# piezo-layer_v0_1-R002.net
KiCad netlist of a schematic drawn in EAGLE
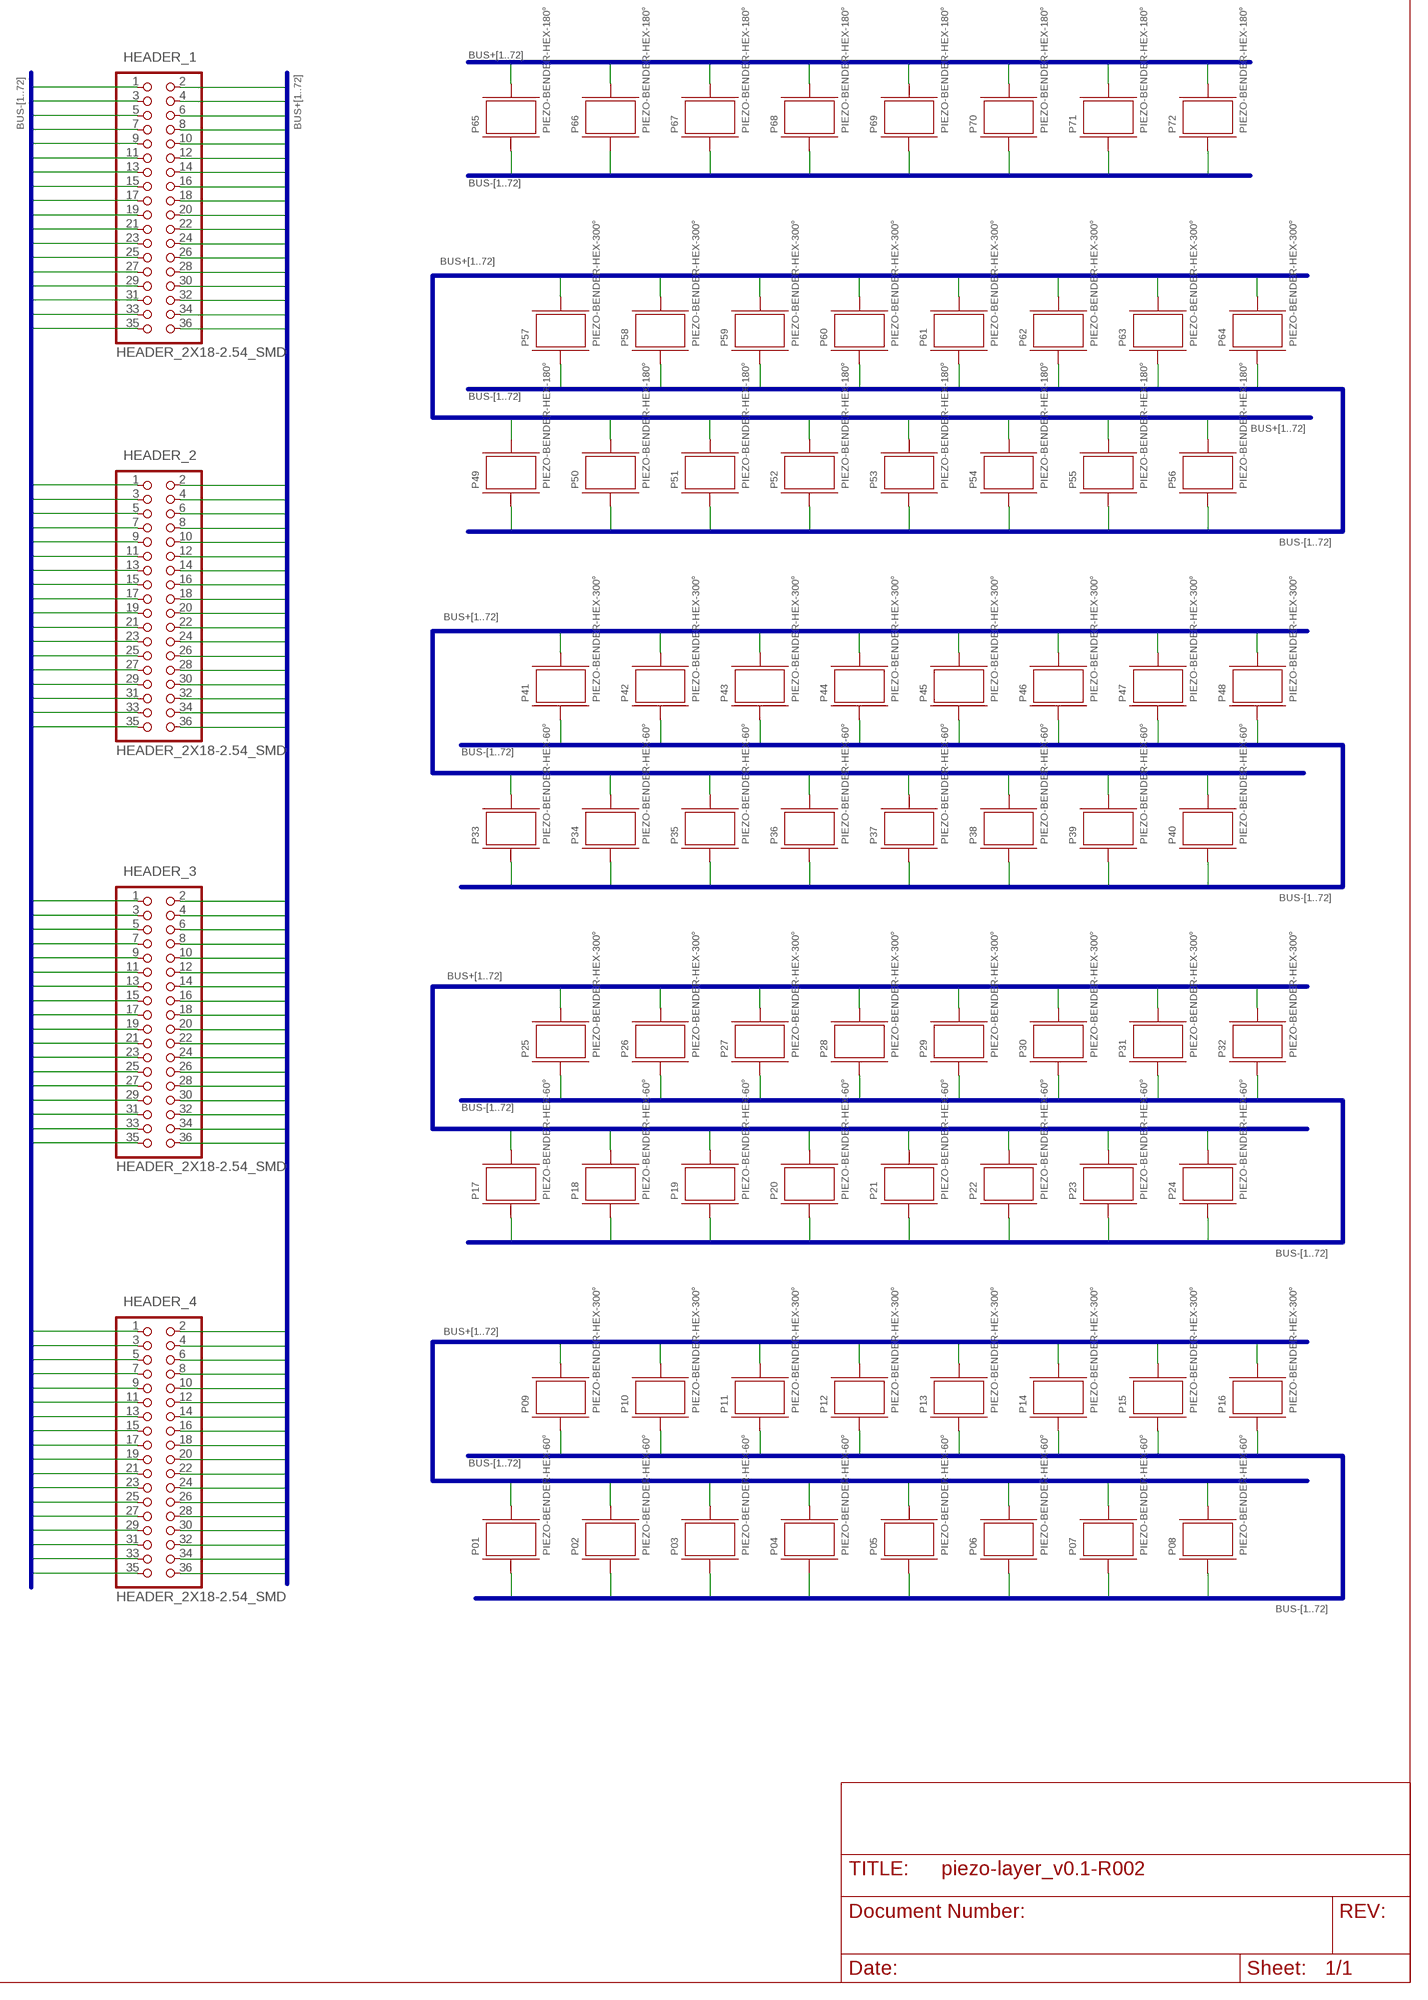
[diagram p0: schematic, sheet 1]

(export (version "E")
  (design (tool "Eeschema 10.0.6"))
  (components
    (comp (ref "HEADER_1")
      (value "HEADER_2X18-2.54_SMD")
      (footprint "eagle-import:2X18_2.54_SMD")
      (libsource (lib "eagle-import") (part "HEADER_2X18-2.54_SMD"))
    )
    (comp (ref "HEADER_2")
      (value "HEADER_2X18-2.54_SMD")
      (footprint "eagle-import:2X18_2.54_SMD")
      (libsource (lib "eagle-import") (part "HEADER_2X18-2.54_SMD"))
    )
    (comp (ref "HEADER_3")
      (value "HEADER_2X18-2.54_SMD")
      (footprint "eagle-import:2X18_2.54_SMD")
      (libsource (lib "eagle-import") (part "HEADER_2X18-2.54_SMD"))
    )
    (comp (ref "HEADER_4")
      (value "HEADER_2X18-2.54_SMD")
      (footprint "eagle-import:2X18_2.54_SMD")
      (libsource (lib "eagle-import") (part "HEADER_2X18-2.54_SMD"))
    )
    (comp (ref "P01")
      (value "PIEZO-BENDER-HEX-60°")
      (footprint "eagle-import:PIEZO-BENDER-HEX_16MM_60°")
      (libsource (lib "eagle-import") (part "PIEZO-BENDER-HEX-60°"))
    )
    (comp (ref "P02")
      (value "PIEZO-BENDER-HEX-60°")
      (footprint "eagle-import:PIEZO-BENDER-HEX_16MM_60°")
      (libsource (lib "eagle-import") (part "PIEZO-BENDER-HEX-60°"))
    )
    (comp (ref "P03")
      (value "PIEZO-BENDER-HEX-60°")
      (footprint "eagle-import:PIEZO-BENDER-HEX_16MM_60°")
      (libsource (lib "eagle-import") (part "PIEZO-BENDER-HEX-60°"))
    )
    (comp (ref "P04")
      (value "PIEZO-BENDER-HEX-60°")
      (footprint "eagle-import:PIEZO-BENDER-HEX_16MM_60°")
      (libsource (lib "eagle-import") (part "PIEZO-BENDER-HEX-60°"))
    )
    (comp (ref "P05")
      (value "PIEZO-BENDER-HEX-60°")
      (footprint "eagle-import:PIEZO-BENDER-HEX_16MM_60°")
      (libsource (lib "eagle-import") (part "PIEZO-BENDER-HEX-60°"))
    )
    (comp (ref "P06")
      (value "PIEZO-BENDER-HEX-60°")
      (footprint "eagle-import:PIEZO-BENDER-HEX_16MM_60°")
      (libsource (lib "eagle-import") (part "PIEZO-BENDER-HEX-60°"))
    )
    (comp (ref "P07")
      (value "PIEZO-BENDER-HEX-60°")
      (footprint "eagle-import:PIEZO-BENDER-HEX_16MM_60°")
      (libsource (lib "eagle-import") (part "PIEZO-BENDER-HEX-60°"))
    )
    (comp (ref "P08")
      (value "PIEZO-BENDER-HEX-60°")
      (footprint "eagle-import:PIEZO-BENDER-HEX_16MM_60°")
      (libsource (lib "eagle-import") (part "PIEZO-BENDER-HEX-60°"))
    )
    (comp (ref "P09")
      (value "PIEZO-BENDER-HEX-300°")
      (footprint "eagle-import:PIEZO-BENDER-HEX_16MM_300°")
      (libsource (lib "eagle-import") (part "PIEZO-BENDER-HEX-300°"))
    )
    (comp (ref "P10")
      (value "PIEZO-BENDER-HEX-300°")
      (footprint "eagle-import:PIEZO-BENDER-HEX_16MM_300°")
      (libsource (lib "eagle-import") (part "PIEZO-BENDER-HEX-300°"))
    )
    (comp (ref "P11")
      (value "PIEZO-BENDER-HEX-300°")
      (footprint "eagle-import:PIEZO-BENDER-HEX_16MM_300°")
      (libsource (lib "eagle-import") (part "PIEZO-BENDER-HEX-300°"))
    )
    (comp (ref "P12")
      (value "PIEZO-BENDER-HEX-300°")
      (footprint "eagle-import:PIEZO-BENDER-HEX_16MM_300°")
      (libsource (lib "eagle-import") (part "PIEZO-BENDER-HEX-300°"))
    )
    (comp (ref "P13")
      (value "PIEZO-BENDER-HEX-300°")
      (footprint "eagle-import:PIEZO-BENDER-HEX_16MM_300°")
      (libsource (lib "eagle-import") (part "PIEZO-BENDER-HEX-300°"))
    )
    (comp (ref "P14")
      (value "PIEZO-BENDER-HEX-300°")
      (footprint "eagle-import:PIEZO-BENDER-HEX_16MM_300°")
      (libsource (lib "eagle-import") (part "PIEZO-BENDER-HEX-300°"))
    )
    (comp (ref "P15")
      (value "PIEZO-BENDER-HEX-300°")
      (footprint "eagle-import:PIEZO-BENDER-HEX_16MM_300°")
      (libsource (lib "eagle-import") (part "PIEZO-BENDER-HEX-300°"))
    )
    (comp (ref "P16")
      (value "PIEZO-BENDER-HEX-300°")
      (footprint "eagle-import:PIEZO-BENDER-HEX_16MM_300°")
      (libsource (lib "eagle-import") (part "PIEZO-BENDER-HEX-300°"))
    )
    (comp (ref "P17")
      (value "PIEZO-BENDER-HEX-60°")
      (footprint "eagle-import:PIEZO-BENDER-HEX_16MM_60°")
      (libsource (lib "eagle-import") (part "PIEZO-BENDER-HEX-60°"))
    )
    (comp (ref "P18")
      (value "PIEZO-BENDER-HEX-60°")
      (footprint "eagle-import:PIEZO-BENDER-HEX_16MM_60°")
      (libsource (lib "eagle-import") (part "PIEZO-BENDER-HEX-60°"))
    )
    (comp (ref "P19")
      (value "PIEZO-BENDER-HEX-60°")
      (footprint "eagle-import:PIEZO-BENDER-HEX_16MM_60°")
      (libsource (lib "eagle-import") (part "PIEZO-BENDER-HEX-60°"))
    )
    (comp (ref "P20")
      (value "PIEZO-BENDER-HEX-60°")
      (footprint "eagle-import:PIEZO-BENDER-HEX_16MM_60°")
      (libsource (lib "eagle-import") (part "PIEZO-BENDER-HEX-60°"))
    )
    (comp (ref "P21")
      (value "PIEZO-BENDER-HEX-60°")
      (footprint "eagle-import:PIEZO-BENDER-HEX_16MM_60°")
      (libsource (lib "eagle-import") (part "PIEZO-BENDER-HEX-60°"))
    )
    (comp (ref "P22")
      (value "PIEZO-BENDER-HEX-60°")
      (footprint "eagle-import:PIEZO-BENDER-HEX_16MM_60°")
      (libsource (lib "eagle-import") (part "PIEZO-BENDER-HEX-60°"))
    )
    (comp (ref "P23")
      (value "PIEZO-BENDER-HEX-60°")
      (footprint "eagle-import:PIEZO-BENDER-HEX_16MM_60°")
      (libsource (lib "eagle-import") (part "PIEZO-BENDER-HEX-60°"))
    )
    (comp (ref "P24")
      (value "PIEZO-BENDER-HEX-60°")
      (footprint "eagle-import:PIEZO-BENDER-HEX_16MM_60°")
      (libsource (lib "eagle-import") (part "PIEZO-BENDER-HEX-60°"))
    )
    (comp (ref "P25")
      (value "PIEZO-BENDER-HEX-300°")
      (footprint "eagle-import:PIEZO-BENDER-HEX_16MM_300°")
      (libsource (lib "eagle-import") (part "PIEZO-BENDER-HEX-300°"))
    )
    (comp (ref "P26")
      (value "PIEZO-BENDER-HEX-300°")
      (footprint "eagle-import:PIEZO-BENDER-HEX_16MM_300°")
      (libsource (lib "eagle-import") (part "PIEZO-BENDER-HEX-300°"))
    )
    (comp (ref "P27")
      (value "PIEZO-BENDER-HEX-300°")
      (footprint "eagle-import:PIEZO-BENDER-HEX_16MM_300°")
      (libsource (lib "eagle-import") (part "PIEZO-BENDER-HEX-300°"))
    )
    (comp (ref "P28")
      (value "PIEZO-BENDER-HEX-300°")
      (footprint "eagle-import:PIEZO-BENDER-HEX_16MM_300°")
      (libsource (lib "eagle-import") (part "PIEZO-BENDER-HEX-300°"))
    )
    (comp (ref "P29")
      (value "PIEZO-BENDER-HEX-300°")
      (footprint "eagle-import:PIEZO-BENDER-HEX_16MM_300°")
      (libsource (lib "eagle-import") (part "PIEZO-BENDER-HEX-300°"))
    )
    (comp (ref "P30")
      (value "PIEZO-BENDER-HEX-300°")
      (footprint "eagle-import:PIEZO-BENDER-HEX_16MM_300°")
      (libsource (lib "eagle-import") (part "PIEZO-BENDER-HEX-300°"))
    )
    (comp (ref "P31")
      (value "PIEZO-BENDER-HEX-300°")
      (footprint "eagle-import:PIEZO-BENDER-HEX_16MM_300°")
      (libsource (lib "eagle-import") (part "PIEZO-BENDER-HEX-300°"))
    )
    (comp (ref "P32")
      (value "PIEZO-BENDER-HEX-300°")
      (footprint "eagle-import:PIEZO-BENDER-HEX_16MM_300°")
      (libsource (lib "eagle-import") (part "PIEZO-BENDER-HEX-300°"))
    )
    (comp (ref "P33")
      (value "PIEZO-BENDER-HEX-60°")
      (footprint "eagle-import:PIEZO-BENDER-HEX_16MM_60°")
      (libsource (lib "eagle-import") (part "PIEZO-BENDER-HEX-60°"))
    )
    (comp (ref "P34")
      (value "PIEZO-BENDER-HEX-60°")
      (footprint "eagle-import:PIEZO-BENDER-HEX_16MM_60°")
      (libsource (lib "eagle-import") (part "PIEZO-BENDER-HEX-60°"))
    )
    (comp (ref "P35")
      (value "PIEZO-BENDER-HEX-60°")
      (footprint "eagle-import:PIEZO-BENDER-HEX_16MM_60°")
      (libsource (lib "eagle-import") (part "PIEZO-BENDER-HEX-60°"))
    )
    (comp (ref "P36")
      (value "PIEZO-BENDER-HEX-60°")
      (footprint "eagle-import:PIEZO-BENDER-HEX_16MM_60°")
      (libsource (lib "eagle-import") (part "PIEZO-BENDER-HEX-60°"))
    )
    (comp (ref "P37")
      (value "PIEZO-BENDER-HEX-60°")
      (footprint "eagle-import:PIEZO-BENDER-HEX_16MM_60°")
      (libsource (lib "eagle-import") (part "PIEZO-BENDER-HEX-60°"))
    )
    (comp (ref "P38")
      (value "PIEZO-BENDER-HEX-60°")
      (footprint "eagle-import:PIEZO-BENDER-HEX_16MM_60°")
      (libsource (lib "eagle-import") (part "PIEZO-BENDER-HEX-60°"))
    )
    (comp (ref "P39")
      (value "PIEZO-BENDER-HEX-60°")
      (footprint "eagle-import:PIEZO-BENDER-HEX_16MM_60°")
      (libsource (lib "eagle-import") (part "PIEZO-BENDER-HEX-60°"))
    )
    (comp (ref "P40")
      (value "PIEZO-BENDER-HEX-60°")
      (footprint "eagle-import:PIEZO-BENDER-HEX_16MM_60°")
      (libsource (lib "eagle-import") (part "PIEZO-BENDER-HEX-60°"))
    )
    (comp (ref "P41")
      (value "PIEZO-BENDER-HEX-300°")
      (footprint "eagle-import:PIEZO-BENDER-HEX_16MM_300°")
      (libsource (lib "eagle-import") (part "PIEZO-BENDER-HEX-300°"))
    )
    (comp (ref "P42")
      (value "PIEZO-BENDER-HEX-300°")
      (footprint "eagle-import:PIEZO-BENDER-HEX_16MM_300°")
      (libsource (lib "eagle-import") (part "PIEZO-BENDER-HEX-300°"))
    )
    (comp (ref "P43")
      (value "PIEZO-BENDER-HEX-300°")
      (footprint "eagle-import:PIEZO-BENDER-HEX_16MM_300°")
      (libsource (lib "eagle-import") (part "PIEZO-BENDER-HEX-300°"))
    )
    (comp (ref "P44")
      (value "PIEZO-BENDER-HEX-300°")
      (footprint "eagle-import:PIEZO-BENDER-HEX_16MM_300°")
      (libsource (lib "eagle-import") (part "PIEZO-BENDER-HEX-300°"))
    )
    (comp (ref "P45")
      (value "PIEZO-BENDER-HEX-300°")
      (footprint "eagle-import:PIEZO-BENDER-HEX_16MM_300°")
      (libsource (lib "eagle-import") (part "PIEZO-BENDER-HEX-300°"))
    )
    (comp (ref "P46")
      (value "PIEZO-BENDER-HEX-300°")
      (footprint "eagle-import:PIEZO-BENDER-HEX_16MM_300°")
      (libsource (lib "eagle-import") (part "PIEZO-BENDER-HEX-300°"))
    )
    (comp (ref "P47")
      (value "PIEZO-BENDER-HEX-300°")
      (footprint "eagle-import:PIEZO-BENDER-HEX_16MM_300°")
      (libsource (lib "eagle-import") (part "PIEZO-BENDER-HEX-300°"))
    )
    (comp (ref "P48")
      (value "PIEZO-BENDER-HEX-300°")
      (footprint "eagle-import:PIEZO-BENDER-HEX_16MM_300°")
      (libsource (lib "eagle-import") (part "PIEZO-BENDER-HEX-300°"))
    )
    (comp (ref "P49")
      (value "PIEZO-BENDER-HEX-180°")
      (footprint "eagle-import:PIEZO-BENDER-HEX_16MM_180°")
      (libsource (lib "eagle-import") (part "PIEZO-BENDER-HEX-180°"))
    )
    (comp (ref "P50")
      (value "PIEZO-BENDER-HEX-180°")
      (footprint "eagle-import:PIEZO-BENDER-HEX_16MM_180°")
      (libsource (lib "eagle-import") (part "PIEZO-BENDER-HEX-180°"))
    )
    (comp (ref "P51")
      (value "PIEZO-BENDER-HEX-180°")
      (footprint "eagle-import:PIEZO-BENDER-HEX_16MM_180°")
      (libsource (lib "eagle-import") (part "PIEZO-BENDER-HEX-180°"))
    )
    (comp (ref "P52")
      (value "PIEZO-BENDER-HEX-180°")
      (footprint "eagle-import:PIEZO-BENDER-HEX_16MM_180°")
      (libsource (lib "eagle-import") (part "PIEZO-BENDER-HEX-180°"))
    )
    (comp (ref "P53")
      (value "PIEZO-BENDER-HEX-180°")
      (footprint "eagle-import:PIEZO-BENDER-HEX_16MM_180°")
      (libsource (lib "eagle-import") (part "PIEZO-BENDER-HEX-180°"))
    )
    (comp (ref "P54")
      (value "PIEZO-BENDER-HEX-180°")
      (footprint "eagle-import:PIEZO-BENDER-HEX_16MM_180°")
      (libsource (lib "eagle-import") (part "PIEZO-BENDER-HEX-180°"))
    )
    (comp (ref "P55")
      (value "PIEZO-BENDER-HEX-180°")
      (footprint "eagle-import:PIEZO-BENDER-HEX_16MM_180°")
      (libsource (lib "eagle-import") (part "PIEZO-BENDER-HEX-180°"))
    )
    (comp (ref "P56")
      (value "PIEZO-BENDER-HEX-180°")
      (footprint "eagle-import:PIEZO-BENDER-HEX_16MM_180°")
      (libsource (lib "eagle-import") (part "PIEZO-BENDER-HEX-180°"))
    )
    (comp (ref "P57")
      (value "PIEZO-BENDER-HEX-300°")
      (footprint "eagle-import:PIEZO-BENDER-HEX_16MM_300°")
      (libsource (lib "eagle-import") (part "PIEZO-BENDER-HEX-300°"))
    )
    (comp (ref "P58")
      (value "PIEZO-BENDER-HEX-300°")
      (footprint "eagle-import:PIEZO-BENDER-HEX_16MM_300°")
      (libsource (lib "eagle-import") (part "PIEZO-BENDER-HEX-300°"))
    )
    (comp (ref "P59")
      (value "PIEZO-BENDER-HEX-300°")
      (footprint "eagle-import:PIEZO-BENDER-HEX_16MM_300°")
      (libsource (lib "eagle-import") (part "PIEZO-BENDER-HEX-300°"))
    )
    (comp (ref "P60")
      (value "PIEZO-BENDER-HEX-300°")
      (footprint "eagle-import:PIEZO-BENDER-HEX_16MM_300°")
      (libsource (lib "eagle-import") (part "PIEZO-BENDER-HEX-300°"))
    )
    (comp (ref "P61")
      (value "PIEZO-BENDER-HEX-300°")
      (footprint "eagle-import:PIEZO-BENDER-HEX_16MM_300°")
      (libsource (lib "eagle-import") (part "PIEZO-BENDER-HEX-300°"))
    )
    (comp (ref "P62")
      (value "PIEZO-BENDER-HEX-300°")
      (footprint "eagle-import:PIEZO-BENDER-HEX_16MM_300°")
      (libsource (lib "eagle-import") (part "PIEZO-BENDER-HEX-300°"))
    )
    (comp (ref "P63")
      (value "PIEZO-BENDER-HEX-300°")
      (footprint "eagle-import:PIEZO-BENDER-HEX_16MM_300°")
      (libsource (lib "eagle-import") (part "PIEZO-BENDER-HEX-300°"))
    )
    (comp (ref "P64")
      (value "PIEZO-BENDER-HEX-300°")
      (footprint "eagle-import:PIEZO-BENDER-HEX_16MM_300°")
      (libsource (lib "eagle-import") (part "PIEZO-BENDER-HEX-300°"))
    )
    (comp (ref "P65")
      (value "PIEZO-BENDER-HEX-180°")
      (footprint "eagle-import:PIEZO-BENDER-HEX_16MM_180°")
      (libsource (lib "eagle-import") (part "PIEZO-BENDER-HEX-180°"))
    )
    (comp (ref "P66")
      (value "PIEZO-BENDER-HEX-180°")
      (footprint "eagle-import:PIEZO-BENDER-HEX_16MM_180°")
      (libsource (lib "eagle-import") (part "PIEZO-BENDER-HEX-180°"))
    )
    (comp (ref "P67")
      (value "PIEZO-BENDER-HEX-180°")
      (footprint "eagle-import:PIEZO-BENDER-HEX_16MM_180°")
      (libsource (lib "eagle-import") (part "PIEZO-BENDER-HEX-180°"))
    )
    (comp (ref "P68")
      (value "PIEZO-BENDER-HEX-180°")
      (footprint "eagle-import:PIEZO-BENDER-HEX_16MM_180°")
      (libsource (lib "eagle-import") (part "PIEZO-BENDER-HEX-180°"))
    )
    (comp (ref "P69")
      (value "PIEZO-BENDER-HEX-180°")
      (footprint "eagle-import:PIEZO-BENDER-HEX_16MM_180°")
      (libsource (lib "eagle-import") (part "PIEZO-BENDER-HEX-180°"))
    )
    (comp (ref "P70")
      (value "PIEZO-BENDER-HEX-180°")
      (footprint "eagle-import:PIEZO-BENDER-HEX_16MM_180°")
      (libsource (lib "eagle-import") (part "PIEZO-BENDER-HEX-180°"))
    )
    (comp (ref "P71")
      (value "PIEZO-BENDER-HEX-180°")
      (footprint "eagle-import:PIEZO-BENDER-HEX_16MM_180°")
      (libsource (lib "eagle-import") (part "PIEZO-BENDER-HEX-180°"))
    )
    (comp (ref "P72")
      (value "PIEZO-BENDER-HEX-180°")
      (footprint "eagle-import:PIEZO-BENDER-HEX_16MM_180°")
      (libsource (lib "eagle-import") (part "PIEZO-BENDER-HEX-180°"))
    )
  )
  (nets
    (net (code "1") (name "/BUS+1") (class "Default")
      (node (ref "HEADER_1") (pin "18") (pinfunction "18_18") (pintype "passive"))
      (node (ref "P01") (pin "TIP1") (pinfunction "+_1_TIP1") (pintype "bidirectional"))
    )
    (net (code "2") (name "/BUS+2") (class "Default")
      (node (ref "HEADER_1") (pin "36") (pinfunction "36_36") (pintype "passive"))
      (node (ref "P02") (pin "TIP1") (pinfunction "+_1_TIP1") (pintype "bidirectional"))
    )
    (net (code "3") (name "/BUS+3") (class "Default")
      (node (ref "HEADER_2") (pin "18") (pinfunction "18_18") (pintype "passive"))
      (node (ref "P03") (pin "TIP1") (pinfunction "+_1_TIP1") (pintype "bidirectional"))
    )
    (net (code "4") (name "/BUS+4") (class "Default")
      (node (ref "HEADER_2") (pin "36") (pinfunction "36_36") (pintype "passive"))
      (node (ref "P04") (pin "TIP1") (pinfunction "+_1_TIP1") (pintype "bidirectional"))
    )
    (net (code "5") (name "/BUS+5") (class "Default")
      (node (ref "HEADER_3") (pin "18") (pinfunction "18_18") (pintype "passive"))
      (node (ref "P05") (pin "TIP1") (pinfunction "+_1_TIP1") (pintype "bidirectional"))
    )
    (net (code "6") (name "/BUS+6") (class "Default")
      (node (ref "HEADER_3") (pin "36") (pinfunction "36_36") (pintype "passive"))
      (node (ref "P06") (pin "TIP1") (pinfunction "+_1_TIP1") (pintype "bidirectional"))
    )
    (net (code "7") (name "/BUS+7") (class "Default")
      (node (ref "HEADER_4") (pin "18") (pinfunction "18_18") (pintype "passive"))
      (node (ref "P07") (pin "TIP1") (pinfunction "+_1_TIP1") (pintype "bidirectional"))
    )
    (net (code "8") (name "/BUS+8") (class "Default")
      (node (ref "HEADER_4") (pin "36") (pinfunction "36_36") (pintype "passive"))
      (node (ref "P08") (pin "TIP1") (pinfunction "+_1_TIP1") (pintype "bidirectional"))
    )
    (net (code "9") (name "/BUS+9") (class "Default")
      (node (ref "HEADER_1") (pin "16") (pinfunction "16_16") (pintype "passive"))
      (node (ref "P09") (pin "TIP1") (pinfunction "+_1_TIP1") (pintype "bidirectional"))
    )
    (net (code "10") (name "/BUS+10") (class "Default")
      (node (ref "HEADER_1") (pin "34") (pinfunction "34_34") (pintype "passive"))
      (node (ref "P10") (pin "TIP1") (pinfunction "+_1_TIP1") (pintype "bidirectional"))
    )
    (net (code "11") (name "/BUS+11") (class "Default")
      (node (ref "HEADER_2") (pin "16") (pinfunction "16_16") (pintype "passive"))
      (node (ref "P11") (pin "TIP1") (pinfunction "+_1_TIP1") (pintype "bidirectional"))
    )
    (net (code "12") (name "/BUS+12") (class "Default")
      (node (ref "HEADER_2") (pin "34") (pinfunction "34_34") (pintype "passive"))
      (node (ref "P12") (pin "TIP1") (pinfunction "+_1_TIP1") (pintype "bidirectional"))
    )
    (net (code "13") (name "/BUS+13") (class "Default")
      (node (ref "HEADER_3") (pin "16") (pinfunction "16_16") (pintype "passive"))
      (node (ref "P13") (pin "TIP1") (pinfunction "+_1_TIP1") (pintype "bidirectional"))
    )
    (net (code "14") (name "/BUS+14") (class "Default")
      (node (ref "HEADER_3") (pin "34") (pinfunction "34_34") (pintype "passive"))
      (node (ref "P14") (pin "TIP1") (pinfunction "+_1_TIP1") (pintype "bidirectional"))
    )
    (net (code "15") (name "/BUS+15") (class "Default")
      (node (ref "HEADER_4") (pin "16") (pinfunction "16_16") (pintype "passive"))
      (node (ref "P15") (pin "TIP1") (pinfunction "+_1_TIP1") (pintype "bidirectional"))
    )
    (net (code "16") (name "/BUS+16") (class "Default")
      (node (ref "HEADER_4") (pin "34") (pinfunction "34_34") (pintype "passive"))
      (node (ref "P16") (pin "TIP1") (pinfunction "+_1_TIP1") (pintype "bidirectional"))
    )
    (net (code "17") (name "/BUS+17") (class "Default")
      (node (ref "HEADER_1") (pin "14") (pinfunction "14_14") (pintype "passive"))
      (node (ref "P17") (pin "TIP1") (pinfunction "+_1_TIP1") (pintype "bidirectional"))
    )
    (net (code "18") (name "/BUS+18") (class "Default")
      (node (ref "HEADER_1") (pin "32") (pinfunction "32_32") (pintype "passive"))
      (node (ref "P18") (pin "TIP1") (pinfunction "+_1_TIP1") (pintype "bidirectional"))
    )
    (net (code "19") (name "/BUS+19") (class "Default")
      (node (ref "HEADER_2") (pin "14") (pinfunction "14_14") (pintype "passive"))
      (node (ref "P19") (pin "TIP1") (pinfunction "+_1_TIP1") (pintype "bidirectional"))
    )
    (net (code "20") (name "/BUS+20") (class "Default")
      (node (ref "HEADER_2") (pin "32") (pinfunction "32_32") (pintype "passive"))
      (node (ref "P20") (pin "TIP1") (pinfunction "+_1_TIP1") (pintype "bidirectional"))
    )
    (net (code "21") (name "/BUS+21") (class "Default")
      (node (ref "HEADER_3") (pin "14") (pinfunction "14_14") (pintype "passive"))
      (node (ref "P21") (pin "TIP1") (pinfunction "+_1_TIP1") (pintype "bidirectional"))
    )
    (net (code "22") (name "/BUS+22") (class "Default")
      (node (ref "HEADER_3") (pin "32") (pinfunction "32_32") (pintype "passive"))
      (node (ref "P22") (pin "TIP1") (pinfunction "+_1_TIP1") (pintype "bidirectional"))
    )
    (net (code "23") (name "/BUS+23") (class "Default")
      (node (ref "HEADER_4") (pin "14") (pinfunction "14_14") (pintype "passive"))
      (node (ref "P23") (pin "TIP1") (pinfunction "+_1_TIP1") (pintype "bidirectional"))
    )
    (net (code "24") (name "/BUS+24") (class "Default")
      (node (ref "HEADER_4") (pin "32") (pinfunction "32_32") (pintype "passive"))
      (node (ref "P24") (pin "TIP1") (pinfunction "+_1_TIP1") (pintype "bidirectional"))
    )
    (net (code "25") (name "/BUS+25") (class "Default")
      (node (ref "HEADER_1") (pin "12") (pinfunction "12_12") (pintype "passive"))
      (node (ref "P25") (pin "TIP1") (pinfunction "+_1_TIP1") (pintype "bidirectional"))
    )
    (net (code "26") (name "/BUS+26") (class "Default")
      (node (ref "HEADER_1") (pin "30") (pinfunction "30_30") (pintype "passive"))
      (node (ref "P26") (pin "TIP1") (pinfunction "+_1_TIP1") (pintype "bidirectional"))
    )
    (net (code "27") (name "/BUS+27") (class "Default")
      (node (ref "HEADER_2") (pin "12") (pinfunction "12_12") (pintype "passive"))
      (node (ref "P27") (pin "TIP1") (pinfunction "+_1_TIP1") (pintype "bidirectional"))
    )
    (net (code "28") (name "/BUS+28") (class "Default")
      (node (ref "HEADER_2") (pin "30") (pinfunction "30_30") (pintype "passive"))
      (node (ref "P28") (pin "TIP1") (pinfunction "+_1_TIP1") (pintype "bidirectional"))
    )
    (net (code "29") (name "/BUS+29") (class "Default")
      (node (ref "HEADER_3") (pin "12") (pinfunction "12_12") (pintype "passive"))
      (node (ref "P29") (pin "TIP1") (pinfunction "+_1_TIP1") (pintype "bidirectional"))
    )
    (net (code "30") (name "/BUS+30") (class "Default")
      (node (ref "HEADER_3") (pin "30") (pinfunction "30_30") (pintype "passive"))
      (node (ref "P30") (pin "TIP1") (pinfunction "+_1_TIP1") (pintype "bidirectional"))
    )
    (net (code "31") (name "/BUS+31") (class "Default")
      (node (ref "HEADER_4") (pin "12") (pinfunction "12_12") (pintype "passive"))
      (node (ref "P31") (pin "TIP1") (pinfunction "+_1_TIP1") (pintype "bidirectional"))
    )
    (net (code "32") (name "/BUS+32") (class "Default")
      (node (ref "HEADER_4") (pin "30") (pinfunction "30_30") (pintype "passive"))
      (node (ref "P32") (pin "TIP1") (pinfunction "+_1_TIP1") (pintype "bidirectional"))
    )
    (net (code "33") (name "/BUS+33") (class "Default")
      (node (ref "HEADER_1") (pin "10") (pinfunction "10_10") (pintype "passive"))
      (node (ref "P33") (pin "TIP1") (pinfunction "+_1_TIP1") (pintype "bidirectional"))
    )
    (net (code "34") (name "/BUS+34") (class "Default")
      (node (ref "HEADER_1") (pin "28") (pinfunction "28_28") (pintype "passive"))
      (node (ref "P34") (pin "TIP1") (pinfunction "+_1_TIP1") (pintype "bidirectional"))
    )
    (net (code "35") (name "/BUS+35") (class "Default")
      (node (ref "HEADER_2") (pin "10") (pinfunction "10_10") (pintype "passive"))
      (node (ref "P35") (pin "TIP1") (pinfunction "+_1_TIP1") (pintype "bidirectional"))
    )
    (net (code "36") (name "/BUS+36") (class "Default")
      (node (ref "HEADER_2") (pin "28") (pinfunction "28_28") (pintype "passive"))
      (node (ref "P36") (pin "TIP1") (pinfunction "+_1_TIP1") (pintype "bidirectional"))
    )
    (net (code "37") (name "/BUS+37") (class "Default")
      (node (ref "HEADER_3") (pin "10") (pinfunction "10_10") (pintype "passive"))
      (node (ref "P37") (pin "TIP1") (pinfunction "+_1_TIP1") (pintype "bidirectional"))
    )
    (net (code "38") (name "/BUS+38") (class "Default")
      (node (ref "HEADER_3") (pin "28") (pinfunction "28_28") (pintype "passive"))
      (node (ref "P38") (pin "TIP1") (pinfunction "+_1_TIP1") (pintype "bidirectional"))
    )
    (net (code "39") (name "/BUS+39") (class "Default")
      (node (ref "HEADER_4") (pin "10") (pinfunction "10_10") (pintype "passive"))
      (node (ref "P39") (pin "TIP1") (pinfunction "+_1_TIP1") (pintype "bidirectional"))
    )
    (net (code "40") (name "/BUS+40") (class "Default")
      (node (ref "HEADER_4") (pin "28") (pinfunction "28_28") (pintype "passive"))
      (node (ref "P40") (pin "TIP1") (pinfunction "+_1_TIP1") (pintype "bidirectional"))
    )
    (net (code "41") (name "/BUS+41") (class "Default")
      (node (ref "HEADER_1") (pin "8") (pinfunction "8_8") (pintype "passive"))
      (node (ref "P41") (pin "TIP1") (pinfunction "+_1_TIP1") (pintype "bidirectional"))
    )
    (net (code "42") (name "/BUS+42") (class "Default")
      (node (ref "HEADER_1") (pin "26") (pinfunction "26_26") (pintype "passive"))
      (node (ref "P42") (pin "TIP1") (pinfunction "+_1_TIP1") (pintype "bidirectional"))
    )
    (net (code "43") (name "/BUS+43") (class "Default")
      (node (ref "HEADER_2") (pin "8") (pinfunction "8_8") (pintype "passive"))
      (node (ref "P43") (pin "TIP1") (pinfunction "+_1_TIP1") (pintype "bidirectional"))
    )
    (net (code "44") (name "/BUS+44") (class "Default")
      (node (ref "HEADER_2") (pin "26") (pinfunction "26_26") (pintype "passive"))
      (node (ref "P44") (pin "TIP1") (pinfunction "+_1_TIP1") (pintype "bidirectional"))
    )
    (net (code "45") (name "/BUS+45") (class "Default")
      (node (ref "HEADER_3") (pin "8") (pinfunction "8_8") (pintype "passive"))
      (node (ref "P45") (pin "TIP1") (pinfunction "+_1_TIP1") (pintype "bidirectional"))
    )
    (net (code "46") (name "/BUS+46") (class "Default")
      (node (ref "HEADER_3") (pin "26") (pinfunction "26_26") (pintype "passive"))
      (node (ref "P46") (pin "TIP1") (pinfunction "+_1_TIP1") (pintype "bidirectional"))
    )
    (net (code "47") (name "/BUS+47") (class "Default")
      (node (ref "HEADER_4") (pin "8") (pinfunction "8_8") (pintype "passive"))
      (node (ref "P47") (pin "TIP1") (pinfunction "+_1_TIP1") (pintype "bidirectional"))
    )
    (net (code "48") (name "/BUS+48") (class "Default")
      (node (ref "HEADER_4") (pin "26") (pinfunction "26_26") (pintype "passive"))
      (node (ref "P48") (pin "TIP1") (pinfunction "+_1_TIP1") (pintype "bidirectional"))
    )
    (net (code "49") (name "/BUS+49") (class "Default")
      (node (ref "HEADER_1") (pin "6") (pinfunction "6_6") (pintype "passive"))
      (node (ref "P49") (pin "TIP1") (pinfunction "+_1_TIP1") (pintype "bidirectional"))
    )
    (net (code "50") (name "/BUS+50") (class "Default")
      (node (ref "HEADER_1") (pin "24") (pinfunction "24_24") (pintype "passive"))
      (node (ref "P50") (pin "TIP1") (pinfunction "+_1_TIP1") (pintype "bidirectional"))
    )
    (net (code "51") (name "/BUS+51") (class "Default")
      (node (ref "HEADER_2") (pin "6") (pinfunction "6_6") (pintype "passive"))
      (node (ref "P51") (pin "TIP1") (pinfunction "+_1_TIP1") (pintype "bidirectional"))
    )
    (net (code "52") (name "/BUS+52") (class "Default")
      (node (ref "HEADER_2") (pin "24") (pinfunction "24_24") (pintype "passive"))
      (node (ref "P52") (pin "TIP1") (pinfunction "+_1_TIP1") (pintype "bidirectional"))
    )
    (net (code "53") (name "/BUS+53") (class "Default")
      (node (ref "HEADER_3") (pin "6") (pinfunction "6_6") (pintype "passive"))
      (node (ref "P53") (pin "TIP1") (pinfunction "+_1_TIP1") (pintype "bidirectional"))
    )
    (net (code "54") (name "/BUS+54") (class "Default")
      (node (ref "HEADER_3") (pin "24") (pinfunction "24_24") (pintype "passive"))
      (node (ref "P54") (pin "TIP1") (pinfunction "+_1_TIP1") (pintype "bidirectional"))
    )
    (net (code "55") (name "/BUS+55") (class "Default")
      (node (ref "HEADER_4") (pin "6") (pinfunction "6_6") (pintype "passive"))
      (node (ref "P55") (pin "TIP1") (pinfunction "+_1_TIP1") (pintype "bidirectional"))
    )
    (net (code "56") (name "/BUS+56") (class "Default")
      (node (ref "HEADER_4") (pin "24") (pinfunction "24_24") (pintype "passive"))
      (node (ref "P56") (pin "TIP1") (pinfunction "+_1_TIP1") (pintype "bidirectional"))
    )
    (net (code "57") (name "/BUS+57") (class "Default")
      (node (ref "HEADER_1") (pin "4") (pinfunction "4_4") (pintype "passive"))
      (node (ref "P57") (pin "TIP1") (pinfunction "+_1_TIP1") (pintype "bidirectional"))
    )
    (net (code "58") (name "/BUS+58") (class "Default")
      (node (ref "HEADER_1") (pin "22") (pinfunction "22_22") (pintype "passive"))
      (node (ref "P58") (pin "TIP1") (pinfunction "+_1_TIP1") (pintype "bidirectional"))
    )
    (net (code "59") (name "/BUS+59") (class "Default")
      (node (ref "HEADER_2") (pin "4") (pinfunction "4_4") (pintype "passive"))
      (node (ref "P59") (pin "TIP1") (pinfunction "+_1_TIP1") (pintype "bidirectional"))
    )
    (net (code "60") (name "/BUS+60") (class "Default")
      (node (ref "HEADER_2") (pin "22") (pinfunction "22_22") (pintype "passive"))
      (node (ref "P60") (pin "TIP1") (pinfunction "+_1_TIP1") (pintype "bidirectional"))
    )
    (net (code "61") (name "/BUS+61") (class "Default")
      (node (ref "HEADER_3") (pin "4") (pinfunction "4_4") (pintype "passive"))
      (node (ref "P61") (pin "TIP1") (pinfunction "+_1_TIP1") (pintype "bidirectional"))
    )
    (net (code "62") (name "/BUS+62") (class "Default")
      (node (ref "HEADER_3") (pin "22") (pinfunction "22_22") (pintype "passive"))
      (node (ref "P62") (pin "TIP1") (pinfunction "+_1_TIP1") (pintype "bidirectional"))
    )
    (net (code "63") (name "/BUS+63") (class "Default")
      (node (ref "HEADER_4") (pin "4") (pinfunction "4_4") (pintype "passive"))
      (node (ref "P63") (pin "TIP1") (pinfunction "+_1_TIP1") (pintype "bidirectional"))
    )
    (net (code "64") (name "/BUS+64") (class "Default")
      (node (ref "HEADER_4") (pin "22") (pinfunction "22_22") (pintype "passive"))
      (node (ref "P64") (pin "TIP1") (pinfunction "+_1_TIP1") (pintype "bidirectional"))
    )
    (net (code "65") (name "/BUS+65") (class "Default")
      (node (ref "HEADER_1") (pin "2") (pinfunction "2_2") (pintype "passive"))
      (node (ref "P65") (pin "TIP1") (pinfunction "+_1_TIP1") (pintype "bidirectional"))
    )
    (net (code "66") (name "/BUS+66") (class "Default")
      (node (ref "HEADER_1") (pin "20") (pinfunction "20_20") (pintype "passive"))
      (node (ref "P66") (pin "TIP1") (pinfunction "+_1_TIP1") (pintype "bidirectional"))
    )
    (net (code "67") (name "/BUS+67") (class "Default")
      (node (ref "HEADER_2") (pin "2") (pinfunction "2_2") (pintype "passive"))
      (node (ref "P67") (pin "TIP1") (pinfunction "+_1_TIP1") (pintype "bidirectional"))
    )
    (net (code "68") (name "/BUS+68") (class "Default")
      (node (ref "HEADER_2") (pin "20") (pinfunction "20_20") (pintype "passive"))
      (node (ref "P68") (pin "TIP1") (pinfunction "+_1_TIP1") (pintype "bidirectional"))
    )
    (net (code "69") (name "/BUS+69") (class "Default")
      (node (ref "HEADER_3") (pin "2") (pinfunction "2_2") (pintype "passive"))
      (node (ref "P69") (pin "TIP1") (pinfunction "+_1_TIP1") (pintype "bidirectional"))
    )
    (net (code "70") (name "/BUS+70") (class "Default")
      (node (ref "HEADER_3") (pin "20") (pinfunction "20_20") (pintype "passive"))
      (node (ref "P70") (pin "TIP1") (pinfunction "+_1_TIP1") (pintype "bidirectional"))
    )
    (net (code "71") (name "/BUS+71") (class "Default")
      (node (ref "HEADER_4") (pin "2") (pinfunction "2_2") (pintype "passive"))
      (node (ref "P71") (pin "TIP1") (pinfunction "+_1_TIP1") (pintype "bidirectional"))
    )
    (net (code "72") (name "/BUS+72") (class "Default")
      (node (ref "HEADER_4") (pin "20") (pinfunction "20_20") (pintype "passive"))
      (node (ref "P72") (pin "TIP1") (pinfunction "+_1_TIP1") (pintype "bidirectional"))
    )
    (net (code "74") (name "/BUS-1") (class "Default")
      (node (ref "HEADER_1") (pin "17") (pinfunction "17_17") (pintype "passive"))
      (node (ref "P01") (pin "PAD1") (pinfunction "-_1_PAD1") (pintype "bidirectional"))
    )
    (net (code "75") (name "/BUS-2") (class "Default")
      (node (ref "HEADER_1") (pin "35") (pinfunction "35_35") (pintype "passive"))
      (node (ref "P02") (pin "PAD1") (pinfunction "-_1_PAD1") (pintype "bidirectional"))
    )
    (net (code "76") (name "/BUS-3") (class "Default")
      (node (ref "HEADER_2") (pin "17") (pinfunction "17_17") (pintype "passive"))
      (node (ref "P03") (pin "PAD1") (pinfunction "-_1_PAD1") (pintype "bidirectional"))
    )
    (net (code "77") (name "/BUS-4") (class "Default")
      (node (ref "HEADER_2") (pin "35") (pinfunction "35_35") (pintype "passive"))
      (node (ref "P04") (pin "PAD1") (pinfunction "-_1_PAD1") (pintype "bidirectional"))
    )
    (net (code "78") (name "/BUS-5") (class "Default")
      (node (ref "HEADER_3") (pin "17") (pinfunction "17_17") (pintype "passive"))
      (node (ref "P05") (pin "PAD1") (pinfunction "-_1_PAD1") (pintype "bidirectional"))
    )
    (net (code "79") (name "/BUS-6") (class "Default")
      (node (ref "HEADER_3") (pin "35") (pinfunction "35_35") (pintype "passive"))
      (node (ref "P06") (pin "PAD1") (pinfunction "-_1_PAD1") (pintype "bidirectional"))
    )
    (net (code "80") (name "/BUS-7") (class "Default")
      (node (ref "HEADER_4") (pin "17") (pinfunction "17_17") (pintype "passive"))
      (node (ref "P07") (pin "PAD1") (pinfunction "-_1_PAD1") (pintype "bidirectional"))
    )
    (net (code "81") (name "/BUS-8") (class "Default")
      (node (ref "HEADER_4") (pin "35") (pinfunction "35_35") (pintype "passive"))
      (node (ref "P08") (pin "PAD1") (pinfunction "-_1_PAD1") (pintype "bidirectional"))
    )
    (net (code "82") (name "/BUS-9") (class "Default")
      (node (ref "HEADER_1") (pin "15") (pinfunction "15_15") (pintype "passive"))
      (node (ref "P09") (pin "PAD1") (pinfunction "-_1_PAD1") (pintype "bidirectional"))
    )
    (net (code "83") (name "/BUS-10") (class "Default")
      (node (ref "HEADER_1") (pin "33") (pinfunction "33_33") (pintype "passive"))
      (node (ref "P10") (pin "PAD1") (pinfunction "-_1_PAD1") (pintype "bidirectional"))
    )
    (net (code "84") (name "/BUS-11") (class "Default")
      (node (ref "HEADER_2") (pin "15") (pinfunction "15_15") (pintype "passive"))
      (node (ref "P11") (pin "PAD1") (pinfunction "-_1_PAD1") (pintype "bidirectional"))
    )
    (net (code "85") (name "/BUS-12") (class "Default")
      (node (ref "HEADER_2") (pin "33") (pinfunction "33_33") (pintype "passive"))
      (node (ref "P12") (pin "PAD1") (pinfunction "-_1_PAD1") (pintype "bidirectional"))
    )
    (net (code "86") (name "/BUS-13") (class "Default")
      (node (ref "HEADER_3") (pin "15") (pinfunction "15_15") (pintype "passive"))
      (node (ref "P13") (pin "PAD1") (pinfunction "-_1_PAD1") (pintype "bidirectional"))
    )
    (net (code "87") (name "/BUS-14") (class "Default")
      (node (ref "HEADER_3") (pin "33") (pinfunction "33_33") (pintype "passive"))
      (node (ref "P14") (pin "PAD1") (pinfunction "-_1_PAD1") (pintype "bidirectional"))
    )
    (net (code "88") (name "/BUS-15") (class "Default")
      (node (ref "HEADER_4") (pin "15") (pinfunction "15_15") (pintype "passive"))
      (node (ref "P15") (pin "PAD1") (pinfunction "-_1_PAD1") (pintype "bidirectional"))
    )
    (net (code "89") (name "/BUS-16") (class "Default")
      (node (ref "HEADER_4") (pin "33") (pinfunction "33_33") (pintype "passive"))
      (node (ref "P16") (pin "PAD1") (pinfunction "-_1_PAD1") (pintype "bidirectional"))
    )
    (net (code "90") (name "/BUS-17") (class "Default")
      (node (ref "HEADER_1") (pin "13") (pinfunction "13_13") (pintype "passive"))
      (node (ref "P17") (pin "PAD1") (pinfunction "-_1_PAD1") (pintype "bidirectional"))
    )
    (net (code "91") (name "/BUS-18") (class "Default")
      (node (ref "HEADER_1") (pin "31") (pinfunction "31_31") (pintype "passive"))
      (node (ref "P18") (pin "PAD1") (pinfunction "-_1_PAD1") (pintype "bidirectional"))
    )
    (net (code "92") (name "/BUS-19") (class "Default")
      (node (ref "HEADER_2") (pin "13") (pinfunction "13_13") (pintype "passive"))
      (node (ref "P19") (pin "PAD1") (pinfunction "-_1_PAD1") (pintype "bidirectional"))
    )
    (net (code "93") (name "/BUS-20") (class "Default")
      (node (ref "HEADER_2") (pin "31") (pinfunction "31_31") (pintype "passive"))
      (node (ref "P20") (pin "PAD1") (pinfunction "-_1_PAD1") (pintype "bidirectional"))
    )
    (net (code "94") (name "/BUS-21") (class "Default")
      (node (ref "HEADER_3") (pin "13") (pinfunction "13_13") (pintype "passive"))
      (node (ref "P21") (pin "PAD1") (pinfunction "-_1_PAD1") (pintype "bidirectional"))
    )
    (net (code "95") (name "/BUS-22") (class "Default")
      (node (ref "HEADER_3") (pin "31") (pinfunction "31_31") (pintype "passive"))
      (node (ref "P22") (pin "PAD1") (pinfunction "-_1_PAD1") (pintype "bidirectional"))
    )
    (net (code "96") (name "/BUS-23") (class "Default")
      (node (ref "HEADER_4") (pin "13") (pinfunction "13_13") (pintype "passive"))
      (node (ref "P23") (pin "PAD1") (pinfunction "-_1_PAD1") (pintype "bidirectional"))
    )
    (net (code "97") (name "/BUS-24") (class "Default")
      (node (ref "HEADER_4") (pin "31") (pinfunction "31_31") (pintype "passive"))
      (node (ref "P24") (pin "PAD1") (pinfunction "-_1_PAD1") (pintype "bidirectional"))
    )
    (net (code "98") (name "/BUS-25") (class "Default")
      (node (ref "HEADER_1") (pin "11") (pinfunction "11_11") (pintype "passive"))
      (node (ref "P25") (pin "PAD1") (pinfunction "-_1_PAD1") (pintype "bidirectional"))
    )
    (net (code "99") (name "/BUS-26") (class "Default")
      (node (ref "HEADER_1") (pin "29") (pinfunction "29_29") (pintype "passive"))
      (node (ref "P26") (pin "PAD1") (pinfunction "-_1_PAD1") (pintype "bidirectional"))
    )
    (net (code "100") (name "/BUS-27") (class "Default")
      (node (ref "HEADER_2") (pin "11") (pinfunction "11_11") (pintype "passive"))
      (node (ref "P27") (pin "PAD1") (pinfunction "-_1_PAD1") (pintype "bidirectional"))
    )
    (net (code "101") (name "/BUS-28") (class "Default")
      (node (ref "HEADER_2") (pin "29") (pinfunction "29_29") (pintype "passive"))
      (node (ref "P28") (pin "PAD1") (pinfunction "-_1_PAD1") (pintype "bidirectional"))
    )
    (net (code "102") (name "/BUS-29") (class "Default")
      (node (ref "HEADER_3") (pin "11") (pinfunction "11_11") (pintype "passive"))
      (node (ref "P29") (pin "PAD1") (pinfunction "-_1_PAD1") (pintype "bidirectional"))
    )
    (net (code "103") (name "/BUS-30") (class "Default")
      (node (ref "HEADER_3") (pin "29") (pinfunction "29_29") (pintype "passive"))
      (node (ref "P30") (pin "PAD1") (pinfunction "-_1_PAD1") (pintype "bidirectional"))
    )
    (net (code "104") (name "/BUS-31") (class "Default")
      (node (ref "HEADER_4") (pin "11") (pinfunction "11_11") (pintype "passive"))
      (node (ref "P31") (pin "PAD1") (pinfunction "-_1_PAD1") (pintype "bidirectional"))
    )
    (net (code "105") (name "/BUS-32") (class "Default")
      (node (ref "HEADER_4") (pin "29") (pinfunction "29_29") (pintype "passive"))
      (node (ref "P32") (pin "PAD1") (pinfunction "-_1_PAD1") (pintype "bidirectional"))
    )
    (net (code "106") (name "/BUS-33") (class "Default")
      (node (ref "HEADER_1") (pin "9") (pinfunction "9_9") (pintype "passive"))
      (node (ref "P33") (pin "PAD1") (pinfunction "-_1_PAD1") (pintype "bidirectional"))
    )
    (net (code "107") (name "/BUS-34") (class "Default")
      (node (ref "HEADER_1") (pin "27") (pinfunction "27_27") (pintype "passive"))
      (node (ref "P34") (pin "PAD1") (pinfunction "-_1_PAD1") (pintype "bidirectional"))
    )
    (net (code "108") (name "/BUS-35") (class "Default")
      (node (ref "HEADER_2") (pin "9") (pinfunction "9_9") (pintype "passive"))
      (node (ref "P35") (pin "PAD1") (pinfunction "-_1_PAD1") (pintype "bidirectional"))
    )
    (net (code "109") (name "/BUS-36") (class "Default")
      (node (ref "HEADER_2") (pin "27") (pinfunction "27_27") (pintype "passive"))
      (node (ref "P36") (pin "PAD1") (pinfunction "-_1_PAD1") (pintype "bidirectional"))
    )
    (net (code "110") (name "/BUS-37") (class "Default")
      (node (ref "HEADER_3") (pin "9") (pinfunction "9_9") (pintype "passive"))
      (node (ref "P37") (pin "PAD1") (pinfunction "-_1_PAD1") (pintype "bidirectional"))
    )
    (net (code "111") (name "/BUS-38") (class "Default")
      (node (ref "HEADER_3") (pin "27") (pinfunction "27_27") (pintype "passive"))
      (node (ref "P38") (pin "PAD1") (pinfunction "-_1_PAD1") (pintype "bidirectional"))
    )
    (net (code "112") (name "/BUS-39") (class "Default")
      (node (ref "HEADER_4") (pin "9") (pinfunction "9_9") (pintype "passive"))
      (node (ref "P39") (pin "PAD1") (pinfunction "-_1_PAD1") (pintype "bidirectional"))
    )
    (net (code "113") (name "/BUS-40") (class "Default")
      (node (ref "HEADER_4") (pin "27") (pinfunction "27_27") (pintype "passive"))
      (node (ref "P40") (pin "PAD1") (pinfunction "-_1_PAD1") (pintype "bidirectional"))
    )
    (net (code "114") (name "/BUS-41") (class "Default")
      (node (ref "HEADER_1") (pin "7") (pinfunction "7_7") (pintype "passive"))
      (node (ref "P41") (pin "PAD1") (pinfunction "-_1_PAD1") (pintype "bidirectional"))
    )
    (net (code "115") (name "/BUS-42") (class "Default")
      (node (ref "HEADER_1") (pin "25") (pinfunction "25_25") (pintype "passive"))
      (node (ref "P42") (pin "PAD1") (pinfunction "-_1_PAD1") (pintype "bidirectional"))
    )
    (net (code "116") (name "/BUS-43") (class "Default")
      (node (ref "HEADER_2") (pin "7") (pinfunction "7_7") (pintype "passive"))
      (node (ref "P43") (pin "PAD1") (pinfunction "-_1_PAD1") (pintype "bidirectional"))
    )
    (net (code "117") (name "/BUS-44") (class "Default")
      (node (ref "HEADER_2") (pin "25") (pinfunction "25_25") (pintype "passive"))
      (node (ref "P44") (pin "PAD1") (pinfunction "-_1_PAD1") (pintype "bidirectional"))
    )
    (net (code "118") (name "/BUS-45") (class "Default")
      (node (ref "HEADER_3") (pin "7") (pinfunction "7_7") (pintype "passive"))
      (node (ref "P45") (pin "PAD1") (pinfunction "-_1_PAD1") (pintype "bidirectional"))
    )
    (net (code "119") (name "/BUS-46") (class "Default")
      (node (ref "HEADER_3") (pin "25") (pinfunction "25_25") (pintype "passive"))
      (node (ref "P46") (pin "PAD1") (pinfunction "-_1_PAD1") (pintype "bidirectional"))
    )
    (net (code "120") (name "/BUS-47") (class "Default")
      (node (ref "HEADER_4") (pin "7") (pinfunction "7_7") (pintype "passive"))
      (node (ref "P47") (pin "PAD1") (pinfunction "-_1_PAD1") (pintype "bidirectional"))
    )
    (net (code "121") (name "/BUS-48") (class "Default")
      (node (ref "HEADER_4") (pin "25") (pinfunction "25_25") (pintype "passive"))
      (node (ref "P48") (pin "PAD1") (pinfunction "-_1_PAD1") (pintype "bidirectional"))
    )
    (net (code "122") (name "/BUS-49") (class "Default")
      (node (ref "HEADER_1") (pin "5") (pinfunction "5_5") (pintype "passive"))
      (node (ref "P49") (pin "PAD1") (pinfunction "-_1_PAD1") (pintype "bidirectional"))
    )
    (net (code "123") (name "/BUS-50") (class "Default")
      (node (ref "HEADER_1") (pin "23") (pinfunction "23_23") (pintype "passive"))
      (node (ref "P50") (pin "PAD1") (pinfunction "-_1_PAD1") (pintype "bidirectional"))
    )
    (net (code "124") (name "/BUS-51") (class "Default")
      (node (ref "HEADER_2") (pin "5") (pinfunction "5_5") (pintype "passive"))
      (node (ref "P51") (pin "PAD1") (pinfunction "-_1_PAD1") (pintype "bidirectional"))
    )
    (net (code "125") (name "/BUS-52") (class "Default")
      (node (ref "HEADER_2") (pin "23") (pinfunction "23_23") (pintype "passive"))
      (node (ref "P52") (pin "PAD1") (pinfunction "-_1_PAD1") (pintype "bidirectional"))
    )
    (net (code "126") (name "/BUS-53") (class "Default")
      (node (ref "HEADER_3") (pin "5") (pinfunction "5_5") (pintype "passive"))
      (node (ref "P53") (pin "PAD1") (pinfunction "-_1_PAD1") (pintype "bidirectional"))
    )
    (net (code "127") (name "/BUS-54") (class "Default")
      (node (ref "HEADER_3") (pin "23") (pinfunction "23_23") (pintype "passive"))
      (node (ref "P54") (pin "PAD1") (pinfunction "-_1_PAD1") (pintype "bidirectional"))
    )
    (net (code "128") (name "/BUS-55") (class "Default")
      (node (ref "HEADER_4") (pin "5") (pinfunction "5_5") (pintype "passive"))
      (node (ref "P55") (pin "PAD1") (pinfunction "-_1_PAD1") (pintype "bidirectional"))
    )
    (net (code "129") (name "/BUS-56") (class "Default")
      (node (ref "HEADER_4") (pin "23") (pinfunction "23_23") (pintype "passive"))
      (node (ref "P56") (pin "PAD1") (pinfunction "-_1_PAD1") (pintype "bidirectional"))
    )
    (net (code "130") (name "/BUS-57") (class "Default")
      (node (ref "HEADER_1") (pin "3") (pinfunction "3_3") (pintype "passive"))
      (node (ref "P57") (pin "PAD1") (pinfunction "-_1_PAD1") (pintype "bidirectional"))
    )
    (net (code "131") (name "/BUS-58") (class "Default")
      (node (ref "HEADER_1") (pin "21") (pinfunction "21_21") (pintype "passive"))
      (node (ref "P58") (pin "PAD1") (pinfunction "-_1_PAD1") (pintype "bidirectional"))
    )
    (net (code "132") (name "/BUS-59") (class "Default")
      (node (ref "HEADER_2") (pin "3") (pinfunction "3_3") (pintype "passive"))
      (node (ref "P59") (pin "PAD1") (pinfunction "-_1_PAD1") (pintype "bidirectional"))
    )
    (net (code "133") (name "/BUS-60") (class "Default")
      (node (ref "HEADER_2") (pin "21") (pinfunction "21_21") (pintype "passive"))
      (node (ref "P60") (pin "PAD1") (pinfunction "-_1_PAD1") (pintype "bidirectional"))
    )
    (net (code "134") (name "/BUS-61") (class "Default")
      (node (ref "HEADER_3") (pin "3") (pinfunction "3_3") (pintype "passive"))
      (node (ref "P61") (pin "PAD1") (pinfunction "-_1_PAD1") (pintype "bidirectional"))
    )
    (net (code "135") (name "/BUS-62") (class "Default")
      (node (ref "HEADER_3") (pin "21") (pinfunction "21_21") (pintype "passive"))
      (node (ref "P62") (pin "PAD1") (pinfunction "-_1_PAD1") (pintype "bidirectional"))
    )
    (net (code "136") (name "/BUS-63") (class "Default")
      (node (ref "HEADER_4") (pin "3") (pinfunction "3_3") (pintype "passive"))
      (node (ref "P63") (pin "PAD1") (pinfunction "-_1_PAD1") (pintype "bidirectional"))
    )
    (net (code "137") (name "/BUS-64") (class "Default")
      (node (ref "HEADER_4") (pin "21") (pinfunction "21_21") (pintype "passive"))
      (node (ref "P64") (pin "PAD1") (pinfunction "-_1_PAD1") (pintype "bidirectional"))
    )
    (net (code "138") (name "/BUS-65") (class "Default")
      (node (ref "HEADER_1") (pin "1") (pinfunction "1_1") (pintype "passive"))
      (node (ref "P65") (pin "PAD1") (pinfunction "-_1_PAD1") (pintype "bidirectional"))
    )
    (net (code "139") (name "/BUS-66") (class "Default")
      (node (ref "HEADER_1") (pin "19") (pinfunction "19_19") (pintype "passive"))
      (node (ref "P66") (pin "PAD1") (pinfunction "-_1_PAD1") (pintype "bidirectional"))
    )
    (net (code "140") (name "/BUS-67") (class "Default")
      (node (ref "HEADER_2") (pin "1") (pinfunction "1_1") (pintype "passive"))
      (node (ref "P67") (pin "PAD1") (pinfunction "-_1_PAD1") (pintype "bidirectional"))
    )
    (net (code "141") (name "/BUS-68") (class "Default")
      (node (ref "HEADER_2") (pin "19") (pinfunction "19_19") (pintype "passive"))
      (node (ref "P68") (pin "PAD1") (pinfunction "-_1_PAD1") (pintype "bidirectional"))
    )
    (net (code "142") (name "/BUS-69") (class "Default")
      (node (ref "HEADER_3") (pin "1") (pinfunction "1_1") (pintype "passive"))
      (node (ref "P69") (pin "PAD1") (pinfunction "-_1_PAD1") (pintype "bidirectional"))
    )
    (net (code "143") (name "/BUS-70") (class "Default")
      (node (ref "HEADER_3") (pin "19") (pinfunction "19_19") (pintype "passive"))
      (node (ref "P70") (pin "PAD1") (pinfunction "-_1_PAD1") (pintype "bidirectional"))
    )
    (net (code "144") (name "/BUS-71") (class "Default")
      (node (ref "HEADER_4") (pin "1") (pinfunction "1_1") (pintype "passive"))
      (node (ref "P71") (pin "PAD1") (pinfunction "-_1_PAD1") (pintype "bidirectional"))
    )
    (net (code "145") (name "/BUS-72") (class "Default")
      (node (ref "HEADER_4") (pin "19") (pinfunction "19_19") (pintype "passive"))
      (node (ref "P72") (pin "PAD1") (pinfunction "-_1_PAD1") (pintype "bidirectional"))
    )
  )
)
